# Ultarsonic_Bourd.net
KiCad netlist of a schematic drawn in Altium Designer
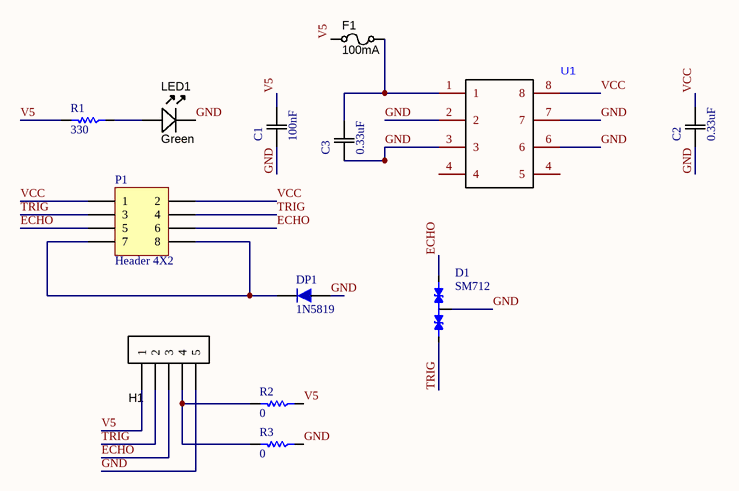
[diagram p0: Ultarsonic_Bourd.SchDoc]

(export (version "E")
  (design (tool "Eeschema 10.0.6"))
  (components
    (comp (ref "C1")
      (value "100nF")
      (footprint "0805")
      (description "CAP CER 0.1UF 50V X7R 0805")
      (fields (field (name "TOLERANCE") "10%"))
      (libsource (lib "AltiumLibraries") (part "CAP 470nF 50V"))
    )
    (comp (ref "C2")
      (value "0.33uF")
      (footprint "0805")
      (description "CAP CER 0.1UF 50V X7R 0805")
      (fields (field (name "TOLERANCE") "10%"))
      (libsource (lib "AltiumLibraries") (part "CAP 470nF 50V"))
    )
    (comp (ref "C3")
      (value "0.33uF")
      (footprint "0805")
      (description "CAP CER 0.1UF 50V X7R 0805")
      (fields (field (name "TOLERANCE") "10%"))
      (libsource (lib "AltiumLibraries") (part "CAP 470nF 50V"))
    )
    (comp (ref "D1")
      (value "SM712")
      (footprint "psm712")
      (description "Asymmetrical TVS Diode for  Extended Common-Mode RS-485")
      (fields (field (name "MANUFACTURER") "SEMTECH") (field (name "MANUFACTURE PART #") "SM712.TC"))
      (libsource (lib "Diode") (part "SM712.TC"))
    )
    (comp (ref "DP1")
      (value "1N5819")
      (footprint "430X270D")
      (description "Schottkey Rectifiers")
      (fields (field (name "DESIGNER") "Abbas Basereh"))
      (libsource (lib "Altium") (part "1N5819"))
    )
    (comp (ref "F1")
      (value "100mA")
      (footprint "RESC3216X70N")
      (description "Fuse 160mA 63VDC 1206 SMD")
      (fields (field (name "Comment") "Slow-blow"))
      (libsource (lib "BPL_Library") (part "FUSE_160mA_1206"))
    )
    (comp (ref "H1")
      (value "Programmer")
      (footprint "HDR1X5_2.54MMP")
      (description "Header 5-pin")
      (libsource (lib "BPL_Library") (part "Header5P"))
    )
    (comp (ref "LED1")
      (value "~")
      (footprint "LED-0805-K")
      (description "LED, 0805 SMD, Green")
      (fields (field (name "COLOR") "Green"))
      (libsource (lib "BPL_Library") (part "LED_SMD_Green_0805_6mcd"))
    )
    (comp (ref "P1")
      (value "Header 4X2")
      (footprint "HDR2X4")
      (description "Header, 4-Pin, Dual row")
      (fields (field (name "PUBLISHER") "Altium Limited"))
      (libsource (lib "Miscellaneous Connectors") (part "Header 4X2"))
    )
    (comp (ref "R1")
      (value "330")
      (footprint "RES 0805 (2012X06L)")
      (description "Resistor")
      (fields (field (name "TOLERANCE") "5%") (field (name "POWER") "1/8 W"))
      (libsource (lib "Electrovolt Lib") (part "Resistor"))
    )
    (comp (ref "R2")
      (value "0")
      (footprint "RES 0805 (2012X06L)")
      (description "Resistor")
      (fields (field (name "TOLERANCE") "5%") (field (name "POWER") "1/8 W"))
      (libsource (lib "Electrovolt Lib") (part "Resistor"))
    )
    (comp (ref "R3")
      (value "0")
      (footprint "RES 0805 (2012X06L)")
      (description "Resistor")
      (fields (field (name "TOLERANCE") "5%") (field (name "POWER") "1/8 W"))
      (libsource (lib "Electrovolt Lib") (part "Resistor"))
    )
    (comp (ref "U1")
      (value "~")
      (footprint "78L05CD15V5V_LIB")
      (libsource (lib "altium-import") (part "root_0_MC78L05ACDG 5V Regulator_"))
    )
  )
  (nets
    (net (code "1") (name "/ECHO") (class "Default")
      (node (ref "D1") (pin "1") (pinfunction "1_1") (pintype "passive"))
      (node (ref "H1") (pin "3") (pinfunction "3_3") (pintype "passive"))
      (node (ref "P1") (pin "5") (pinfunction "5_5") (pintype "passive"))
      (node (ref "P1") (pin "6") (pinfunction "6_6") (pintype "passive"))
    )
    (net (code "2") (name "/GND") (class "Default")
      (node (ref "C1") (pin "1") (pinfunction "C1_1") (pintype "passive"))
      (node (ref "C2") (pin "1") (pinfunction "C1_1") (pintype "passive"))
      (node (ref "C3") (pin "1") (pinfunction "C1_1") (pintype "passive"))
      (node (ref "D1") (pin "3") (pinfunction "3_3") (pintype "passive"))
      (node (ref "DP1") (pin "1") (pintype "passive"))
      (node (ref "H1") (pin "5") (pinfunction "5_5") (pintype "passive"))
      (node (ref "LED1") (pin "K") (pinfunction "K_K") (pintype "passive"))
      (node (ref "R3") (pin "1") (pinfunction "1_1") (pintype "passive"))
      (node (ref "U1") (pin "2") (pinfunction "2_2") (pintype "passive"))
      (node (ref "U1") (pin "3") (pinfunction "3_3") (pintype "passive"))
      (node (ref "U1") (pin "6") (pinfunction "6_6") (pintype "passive"))
      (node (ref "U1") (pin "7") (pinfunction "7_7") (pintype "passive"))
    )
    (net (code "3") (name "/TRIG") (class "Default")
      (node (ref "D1") (pin "2") (pinfunction "2_2") (pintype "passive"))
      (node (ref "H1") (pin "2") (pinfunction "2_2") (pintype "passive"))
      (node (ref "P1") (pin "3") (pinfunction "3_3") (pintype "passive"))
      (node (ref "P1") (pin "4") (pinfunction "4_4") (pintype "passive"))
    )
    (net (code "4") (name "/V5") (class "Default")
      (node (ref "C1") (pin "2") (pinfunction "C2_2") (pintype "passive"))
      (node (ref "F1") (pin "2") (pinfunction "2_2") (pintype "passive"))
      (node (ref "H1") (pin "1") (pinfunction "1_1") (pintype "passive"))
      (node (ref "R1") (pin "2") (pinfunction "2_2") (pintype "passive"))
      (node (ref "R2") (pin "1") (pinfunction "1_1") (pintype "passive"))
    )
    (net (code "5") (name "/VCC") (class "Default")
      (node (ref "C2") (pin "2") (pinfunction "C2_2") (pintype "passive"))
      (node (ref "P1") (pin "1") (pinfunction "1_1") (pintype "passive"))
      (node (ref "P1") (pin "2") (pinfunction "2_2") (pintype "passive"))
      (node (ref "U1") (pin "8") (pinfunction "8_8") (pintype "passive"))
    )
    (net (code "6") (name "Net-(C3-C2)") (class "Default")
      (node (ref "C3") (pin "2") (pinfunction "C2_2") (pintype "passive"))
      (node (ref "F1") (pin "1") (pinfunction "1_1") (pintype "passive"))
      (node (ref "U1") (pin "1") (pinfunction "1_1") (pintype "passive"))
    )
    (net (code "7") (name "Net-(DP1-Pad2)") (class "Default")
      (node (ref "DP1") (pin "2") (pintype "passive"))
      (node (ref "P1") (pin "7") (pinfunction "7_7") (pintype "passive"))
      (node (ref "P1") (pin "8") (pinfunction "8_8") (pintype "passive"))
    )
    (net (code "8") (name "Net-(H1-Pad4)") (class "Default")
      (node (ref "H1") (pin "4") (pinfunction "4_4") (pintype "passive"))
      (node (ref "R2") (pin "2") (pinfunction "2_2") (pintype "passive"))
      (node (ref "R3") (pin "2") (pinfunction "2_2") (pintype "passive"))
    )
    (net (code "9") (name "Net-(LED1-PadA)") (class "Default")
      (node (ref "LED1") (pin "A") (pinfunction "A_A") (pintype "passive"))
      (node (ref "R1") (pin "1") (pinfunction "1_1") (pintype "passive"))
    )
    (net (code "10") (name "unconnected-(U1-5-Pad4)") (class "Default")
      (node (ref "U1") (pin "4") (pinfunction "5_4") (pintype "passive"))
    )
    (net (code "11") (name "unconnected-(U1-Pad4)") (class "Default")
      (node (ref "U1") (pin "4") (pinfunction "4_4") (pintype "passive"))
    )
  )
)
